# Hive_Monitor_MEGA_shield.net
KiCad netlist of a schematic drawn in EAGLE
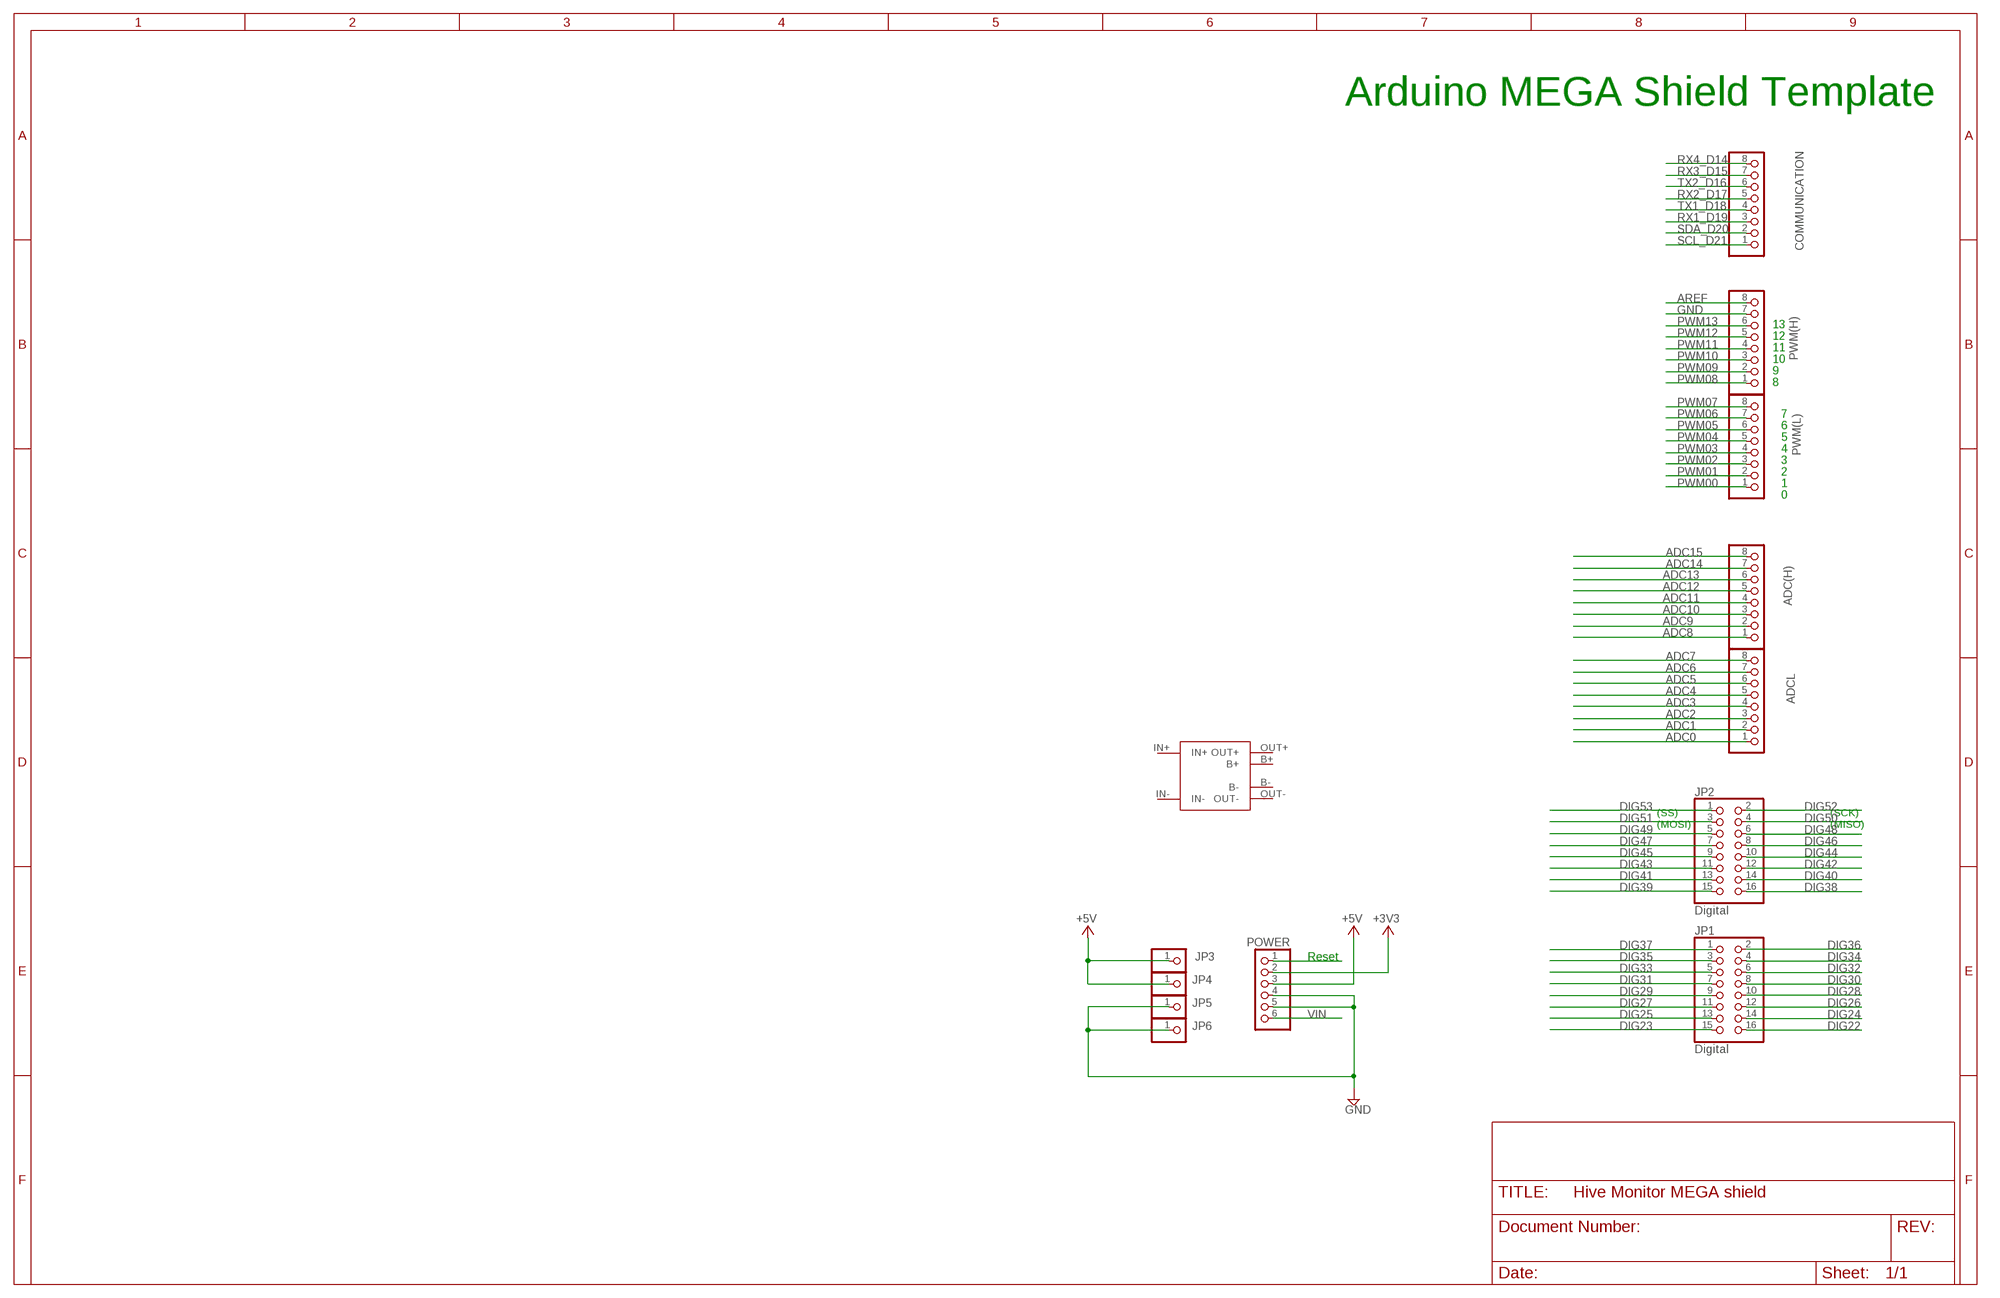
[diagram p0: schematic, sheet 1]

(export (version "E")
  (design (tool "Eeschema 10.0.6"))
  (components
    (comp (ref "ADC(H)")
      (value "PINHD-1X8")
      (footprint "eagle-import:1X08")
      (libsource (lib "eagle-import") (part "PINHD-1X8"))
    )
    (comp (ref "ADCL")
      (value "PINHD-1X8")
      (footprint "eagle-import:1X08")
      (libsource (lib "eagle-import") (part "PINHD-1X8"))
    )
    (comp (ref "COMMUNICATION")
      (value "PINHD-1X8")
      (footprint "eagle-import:1X08")
      (libsource (lib "eagle-import") (part "PINHD-1X8"))
    )
    (comp (ref "JP1")
      (value "Digital")
      (footprint "eagle-import:2X08")
      (libsource (lib "eagle-import") (part "PINHD-2X8"))
    )
    (comp (ref "JP2")
      (value "Digital")
      (footprint "eagle-import:2X08")
      (libsource (lib "eagle-import") (part "PINHD-2X8"))
    )
    (comp (ref "JP3")
      (value "PINHD-1X1")
      (footprint "eagle-import:1X01")
      (libsource (lib "eagle-import") (part "PINHD-1X1"))
    )
    (comp (ref "JP4")
      (value "PINHD-1X1")
      (footprint "eagle-import:1X01")
      (libsource (lib "eagle-import") (part "PINHD-1X1"))
    )
    (comp (ref "JP5")
      (value "PINHD-1X1")
      (footprint "eagle-import:1X01")
      (libsource (lib "eagle-import") (part "PINHD-1X1"))
    )
    (comp (ref "JP6")
      (value "PINHD-1X1")
      (footprint "eagle-import:1X01")
      (libsource (lib "eagle-import") (part "PINHD-1X1"))
    )
    (comp (ref "POWER")
      (value "PINHD-1X6")
      (footprint "eagle-import:1X06")
      (libsource (lib "eagle-import") (part "PINHD-1X6"))
    )
    (comp (ref "PWM(H)")
      (value "PINHD-1X8")
      (footprint "eagle-import:1X08")
      (libsource (lib "eagle-import") (part "PINHD-1X8"))
    )
    (comp (ref "PWM(L)")
      (value "PINHD-1X8")
      (footprint "eagle-import:1X08")
      (libsource (lib "eagle-import") (part "PINHD-1X8"))
    )
    (comp (ref "U$1")
      (value "TP4056-MODULE")
      (footprint "eagle-import:TP4056-LITHIUM-PROTECTED-MODULE")
      (libsource (lib "eagle-import") (part "TP4056-MODULE"))
    )
  )
  (nets
    (net (code "1") (name "+3V3") (class "Default")
      (node (ref "POWER") (pin "2") (pinfunction "2_2") (pintype "passive"))
    )
    (net (code "2") (name "+5V") (class "Default")
      (node (ref "JP3") (pin "1") (pinfunction "1_1") (pintype "passive"))
      (node (ref "JP4") (pin "1") (pinfunction "1_1") (pintype "passive"))
      (node (ref "POWER") (pin "3") (pinfunction "3_3") (pintype "passive"))
    )
    (net (code "3") (name "/ADC0") (class "Default")
      (node (ref "ADCL") (pin "1") (pinfunction "1_1") (pintype "passive"))
    )
    (net (code "4") (name "/ADC1") (class "Default")
      (node (ref "ADCL") (pin "2") (pinfunction "2_2") (pintype "passive"))
    )
    (net (code "5") (name "/ADC2") (class "Default")
      (node (ref "ADCL") (pin "3") (pinfunction "3_3") (pintype "passive"))
    )
    (net (code "6") (name "/ADC3") (class "Default")
      (node (ref "ADCL") (pin "4") (pinfunction "4_4") (pintype "passive"))
    )
    (net (code "7") (name "/ADC4") (class "Default")
      (node (ref "ADCL") (pin "5") (pinfunction "5_5") (pintype "passive"))
    )
    (net (code "8") (name "/ADC5") (class "Default")
      (node (ref "ADCL") (pin "6") (pinfunction "6_6") (pintype "passive"))
    )
    (net (code "9") (name "/ADC6") (class "Default")
      (node (ref "ADCL") (pin "7") (pinfunction "7_7") (pintype "passive"))
    )
    (net (code "10") (name "/ADC7") (class "Default")
      (node (ref "ADCL") (pin "8") (pinfunction "8_8") (pintype "passive"))
    )
    (net (code "11") (name "/ADC8") (class "Default")
      (node (ref "ADC(H)") (pin "1") (pinfunction "1_1") (pintype "passive"))
    )
    (net (code "12") (name "/ADC9") (class "Default")
      (node (ref "ADC(H)") (pin "2") (pinfunction "2_2") (pintype "passive"))
    )
    (net (code "13") (name "/ADC10") (class "Default")
      (node (ref "ADC(H)") (pin "3") (pinfunction "3_3") (pintype "passive"))
    )
    (net (code "14") (name "/ADC11") (class "Default")
      (node (ref "ADC(H)") (pin "4") (pinfunction "4_4") (pintype "passive"))
    )
    (net (code "15") (name "/ADC12") (class "Default")
      (node (ref "ADC(H)") (pin "5") (pinfunction "5_5") (pintype "passive"))
    )
    (net (code "16") (name "/ADC13") (class "Default")
      (node (ref "ADC(H)") (pin "6") (pinfunction "6_6") (pintype "passive"))
    )
    (net (code "17") (name "/ADC14") (class "Default")
      (node (ref "ADC(H)") (pin "7") (pinfunction "7_7") (pintype "passive"))
    )
    (net (code "18") (name "/ADC15") (class "Default")
      (node (ref "ADC(H)") (pin "8") (pinfunction "8_8") (pintype "passive"))
    )
    (net (code "19") (name "/AREF") (class "Default")
      (node (ref "PWM(H)") (pin "8") (pinfunction "8_8") (pintype "passive"))
    )
    (net (code "20") (name "/B+") (class "Default")
      (node (ref "U$1") (pin "B+") (pinfunction "B+_B+") (pintype "power_in"))
    )
    (net (code "21") (name "/B-") (class "Default")
      (node (ref "U$1") (pin "B-") (pinfunction "B-_B-") (pintype "power_in"))
    )
    (net (code "22") (name "/DIG22") (class "Default")
      (node (ref "JP1") (pin "16") (pinfunction "16_16") (pintype "passive"))
    )
    (net (code "23") (name "/DIG23") (class "Default")
      (node (ref "JP1") (pin "15") (pinfunction "15_15") (pintype "passive"))
    )
    (net (code "24") (name "/DIG24") (class "Default")
      (node (ref "JP1") (pin "14") (pinfunction "14_14") (pintype "passive"))
    )
    (net (code "25") (name "/DIG25") (class "Default")
      (node (ref "JP1") (pin "13") (pinfunction "13_13") (pintype "passive"))
    )
    (net (code "26") (name "/DIG26") (class "Default")
      (node (ref "JP1") (pin "12") (pinfunction "12_12") (pintype "passive"))
    )
    (net (code "27") (name "/DIG27") (class "Default")
      (node (ref "JP1") (pin "11") (pinfunction "11_11") (pintype "passive"))
    )
    (net (code "28") (name "/DIG28") (class "Default")
      (node (ref "JP1") (pin "10") (pinfunction "10_10") (pintype "passive"))
    )
    (net (code "29") (name "/DIG29") (class "Default")
      (node (ref "JP1") (pin "9") (pinfunction "9_9") (pintype "passive"))
    )
    (net (code "30") (name "/DIG30") (class "Default")
      (node (ref "JP1") (pin "8") (pinfunction "8_8") (pintype "passive"))
    )
    (net (code "31") (name "/DIG31") (class "Default")
      (node (ref "JP1") (pin "7") (pinfunction "7_7") (pintype "passive"))
    )
    (net (code "32") (name "/DIG32") (class "Default")
      (node (ref "JP1") (pin "6") (pinfunction "6_6") (pintype "passive"))
    )
    (net (code "33") (name "/DIG33") (class "Default")
      (node (ref "JP1") (pin "5") (pinfunction "5_5") (pintype "passive"))
    )
    (net (code "34") (name "/DIG34") (class "Default")
      (node (ref "JP1") (pin "4") (pinfunction "4_4") (pintype "passive"))
    )
    (net (code "35") (name "/DIG35") (class "Default")
      (node (ref "JP1") (pin "3") (pinfunction "3_3") (pintype "passive"))
    )
    (net (code "36") (name "/DIG36") (class "Default")
      (node (ref "JP1") (pin "2") (pinfunction "2_2") (pintype "passive"))
    )
    (net (code "37") (name "/DIG37") (class "Default")
      (node (ref "JP1") (pin "1") (pinfunction "1_1") (pintype "passive"))
    )
    (net (code "38") (name "/DIG38") (class "Default")
      (node (ref "JP2") (pin "16") (pinfunction "16_16") (pintype "passive"))
    )
    (net (code "39") (name "/DIG39") (class "Default")
      (node (ref "JP2") (pin "15") (pinfunction "15_15") (pintype "passive"))
    )
    (net (code "40") (name "/DIG40") (class "Default")
      (node (ref "JP2") (pin "14") (pinfunction "14_14") (pintype "passive"))
    )
    (net (code "41") (name "/DIG41") (class "Default")
      (node (ref "JP2") (pin "13") (pinfunction "13_13") (pintype "passive"))
    )
    (net (code "42") (name "/DIG42") (class "Default")
      (node (ref "JP2") (pin "12") (pinfunction "12_12") (pintype "passive"))
    )
    (net (code "43") (name "/DIG43") (class "Default")
      (node (ref "JP2") (pin "11") (pinfunction "11_11") (pintype "passive"))
    )
    (net (code "44") (name "/DIG44") (class "Default")
      (node (ref "JP2") (pin "10") (pinfunction "10_10") (pintype "passive"))
    )
    (net (code "45") (name "/DIG45") (class "Default")
      (node (ref "JP2") (pin "9") (pinfunction "9_9") (pintype "passive"))
    )
    (net (code "46") (name "/DIG46") (class "Default")
      (node (ref "JP2") (pin "8") (pinfunction "8_8") (pintype "passive"))
    )
    (net (code "47") (name "/DIG47") (class "Default")
      (node (ref "JP2") (pin "7") (pinfunction "7_7") (pintype "passive"))
    )
    (net (code "48") (name "/DIG48") (class "Default")
      (node (ref "JP2") (pin "6") (pinfunction "6_6") (pintype "passive"))
    )
    (net (code "49") (name "/DIG49") (class "Default")
      (node (ref "JP2") (pin "5") (pinfunction "5_5") (pintype "passive"))
    )
    (net (code "50") (name "/DIG50") (class "Default")
      (node (ref "JP2") (pin "4") (pinfunction "4_4") (pintype "passive"))
    )
    (net (code "51") (name "/DIG51") (class "Default")
      (node (ref "JP2") (pin "3") (pinfunction "3_3") (pintype "passive"))
    )
    (net (code "52") (name "/DIG52") (class "Default")
      (node (ref "JP2") (pin "2") (pinfunction "2_2") (pintype "passive"))
    )
    (net (code "53") (name "/DIG53") (class "Default")
      (node (ref "JP2") (pin "1") (pinfunction "1_1") (pintype "passive"))
    )
    (net (code "54") (name "/IN+") (class "Default")
      (node (ref "U$1") (pin "IN+") (pinfunction "IN+_IN+") (pintype "power_in"))
    )
    (net (code "55") (name "/IN-") (class "Default")
      (node (ref "U$1") (pin "IN-") (pinfunction "IN-_IN-") (pintype "power_in"))
    )
    (net (code "56") (name "/OUT+") (class "Default")
      (node (ref "U$1") (pin "OUT+") (pinfunction "OUT+_OUT+") (pintype "power_in"))
    )
    (net (code "57") (name "/OUT-") (class "Default")
      (node (ref "U$1") (pin "OUT-") (pinfunction "OUT-_OUT-") (pintype "power_in"))
    )
    (net (code "58") (name "/PWM00") (class "Default")
      (node (ref "PWM(L)") (pin "1") (pinfunction "1_1") (pintype "passive"))
    )
    (net (code "59") (name "/PWM01") (class "Default")
      (node (ref "PWM(L)") (pin "2") (pinfunction "2_2") (pintype "passive"))
    )
    (net (code "60") (name "/PWM02") (class "Default")
      (node (ref "PWM(L)") (pin "3") (pinfunction "3_3") (pintype "passive"))
    )
    (net (code "61") (name "/PWM03") (class "Default")
      (node (ref "PWM(L)") (pin "4") (pinfunction "4_4") (pintype "passive"))
    )
    (net (code "62") (name "/PWM04") (class "Default")
      (node (ref "PWM(L)") (pin "5") (pinfunction "5_5") (pintype "passive"))
    )
    (net (code "63") (name "/PWM05") (class "Default")
      (node (ref "PWM(L)") (pin "6") (pinfunction "6_6") (pintype "passive"))
    )
    (net (code "64") (name "/PWM06") (class "Default")
      (node (ref "PWM(L)") (pin "7") (pinfunction "7_7") (pintype "passive"))
    )
    (net (code "65") (name "/PWM07") (class "Default")
      (node (ref "PWM(L)") (pin "8") (pinfunction "8_8") (pintype "passive"))
    )
    (net (code "66") (name "/PWM08") (class "Default")
      (node (ref "PWM(H)") (pin "1") (pinfunction "1_1") (pintype "passive"))
    )
    (net (code "67") (name "/PWM09") (class "Default")
      (node (ref "PWM(H)") (pin "2") (pinfunction "2_2") (pintype "passive"))
    )
    (net (code "68") (name "/PWM10") (class "Default")
      (node (ref "PWM(H)") (pin "3") (pinfunction "3_3") (pintype "passive"))
    )
    (net (code "69") (name "/PWM11") (class "Default")
      (node (ref "PWM(H)") (pin "4") (pinfunction "4_4") (pintype "passive"))
    )
    (net (code "70") (name "/PWM12") (class "Default")
      (node (ref "PWM(H)") (pin "5") (pinfunction "5_5") (pintype "passive"))
    )
    (net (code "71") (name "/PWM13") (class "Default")
      (node (ref "PWM(H)") (pin "6") (pinfunction "6_6") (pintype "passive"))
    )
    (net (code "72") (name "/RX1_D19") (class "Default")
      (node (ref "COMMUNICATION") (pin "3") (pinfunction "3_3") (pintype "passive"))
    )
    (net (code "73") (name "/RX2_D17") (class "Default")
      (node (ref "COMMUNICATION") (pin "5") (pinfunction "5_5") (pintype "passive"))
    )
    (net (code "74") (name "/RX3_D15") (class "Default")
      (node (ref "COMMUNICATION") (pin "7") (pinfunction "7_7") (pintype "passive"))
    )
    (net (code "75") (name "/RX4_D14") (class "Default")
      (node (ref "COMMUNICATION") (pin "8") (pinfunction "8_8") (pintype "passive"))
    )
    (net (code "76") (name "/SCL_D21") (class "Default")
      (node (ref "COMMUNICATION") (pin "1") (pinfunction "1_1") (pintype "passive"))
    )
    (net (code "77") (name "/SDA_D20") (class "Default")
      (node (ref "COMMUNICATION") (pin "2") (pinfunction "2_2") (pintype "passive"))
    )
    (net (code "78") (name "/TX1_D18") (class "Default")
      (node (ref "COMMUNICATION") (pin "4") (pinfunction "4_4") (pintype "passive"))
    )
    (net (code "79") (name "/TX2_D16") (class "Default")
      (node (ref "COMMUNICATION") (pin "6") (pinfunction "6_6") (pintype "passive"))
    )
    (net (code "80") (name "/VIN") (class "Default")
      (node (ref "POWER") (pin "6") (pinfunction "6_6") (pintype "passive"))
    )
    (net (code "81") (name "GND") (class "Default")
      (node (ref "JP5") (pin "1") (pinfunction "1_1") (pintype "passive"))
      (node (ref "JP6") (pin "1") (pinfunction "1_1") (pintype "passive"))
      (node (ref "POWER") (pin "4") (pinfunction "4_4") (pintype "passive"))
      (node (ref "POWER") (pin "5") (pinfunction "5_5") (pintype "passive"))
      (node (ref "PWM(H)") (pin "7") (pinfunction "7_7") (pintype "passive"))
    )
    (net (code "82") (name "unconnected-(POWER-Pad1)") (class "Default")
      (node (ref "POWER") (pin "1") (pinfunction "1_1") (pintype "passive"))
    )
  )
)
